# MidDac.net
KiCad netlist of a schematic drawn in Altium Designer
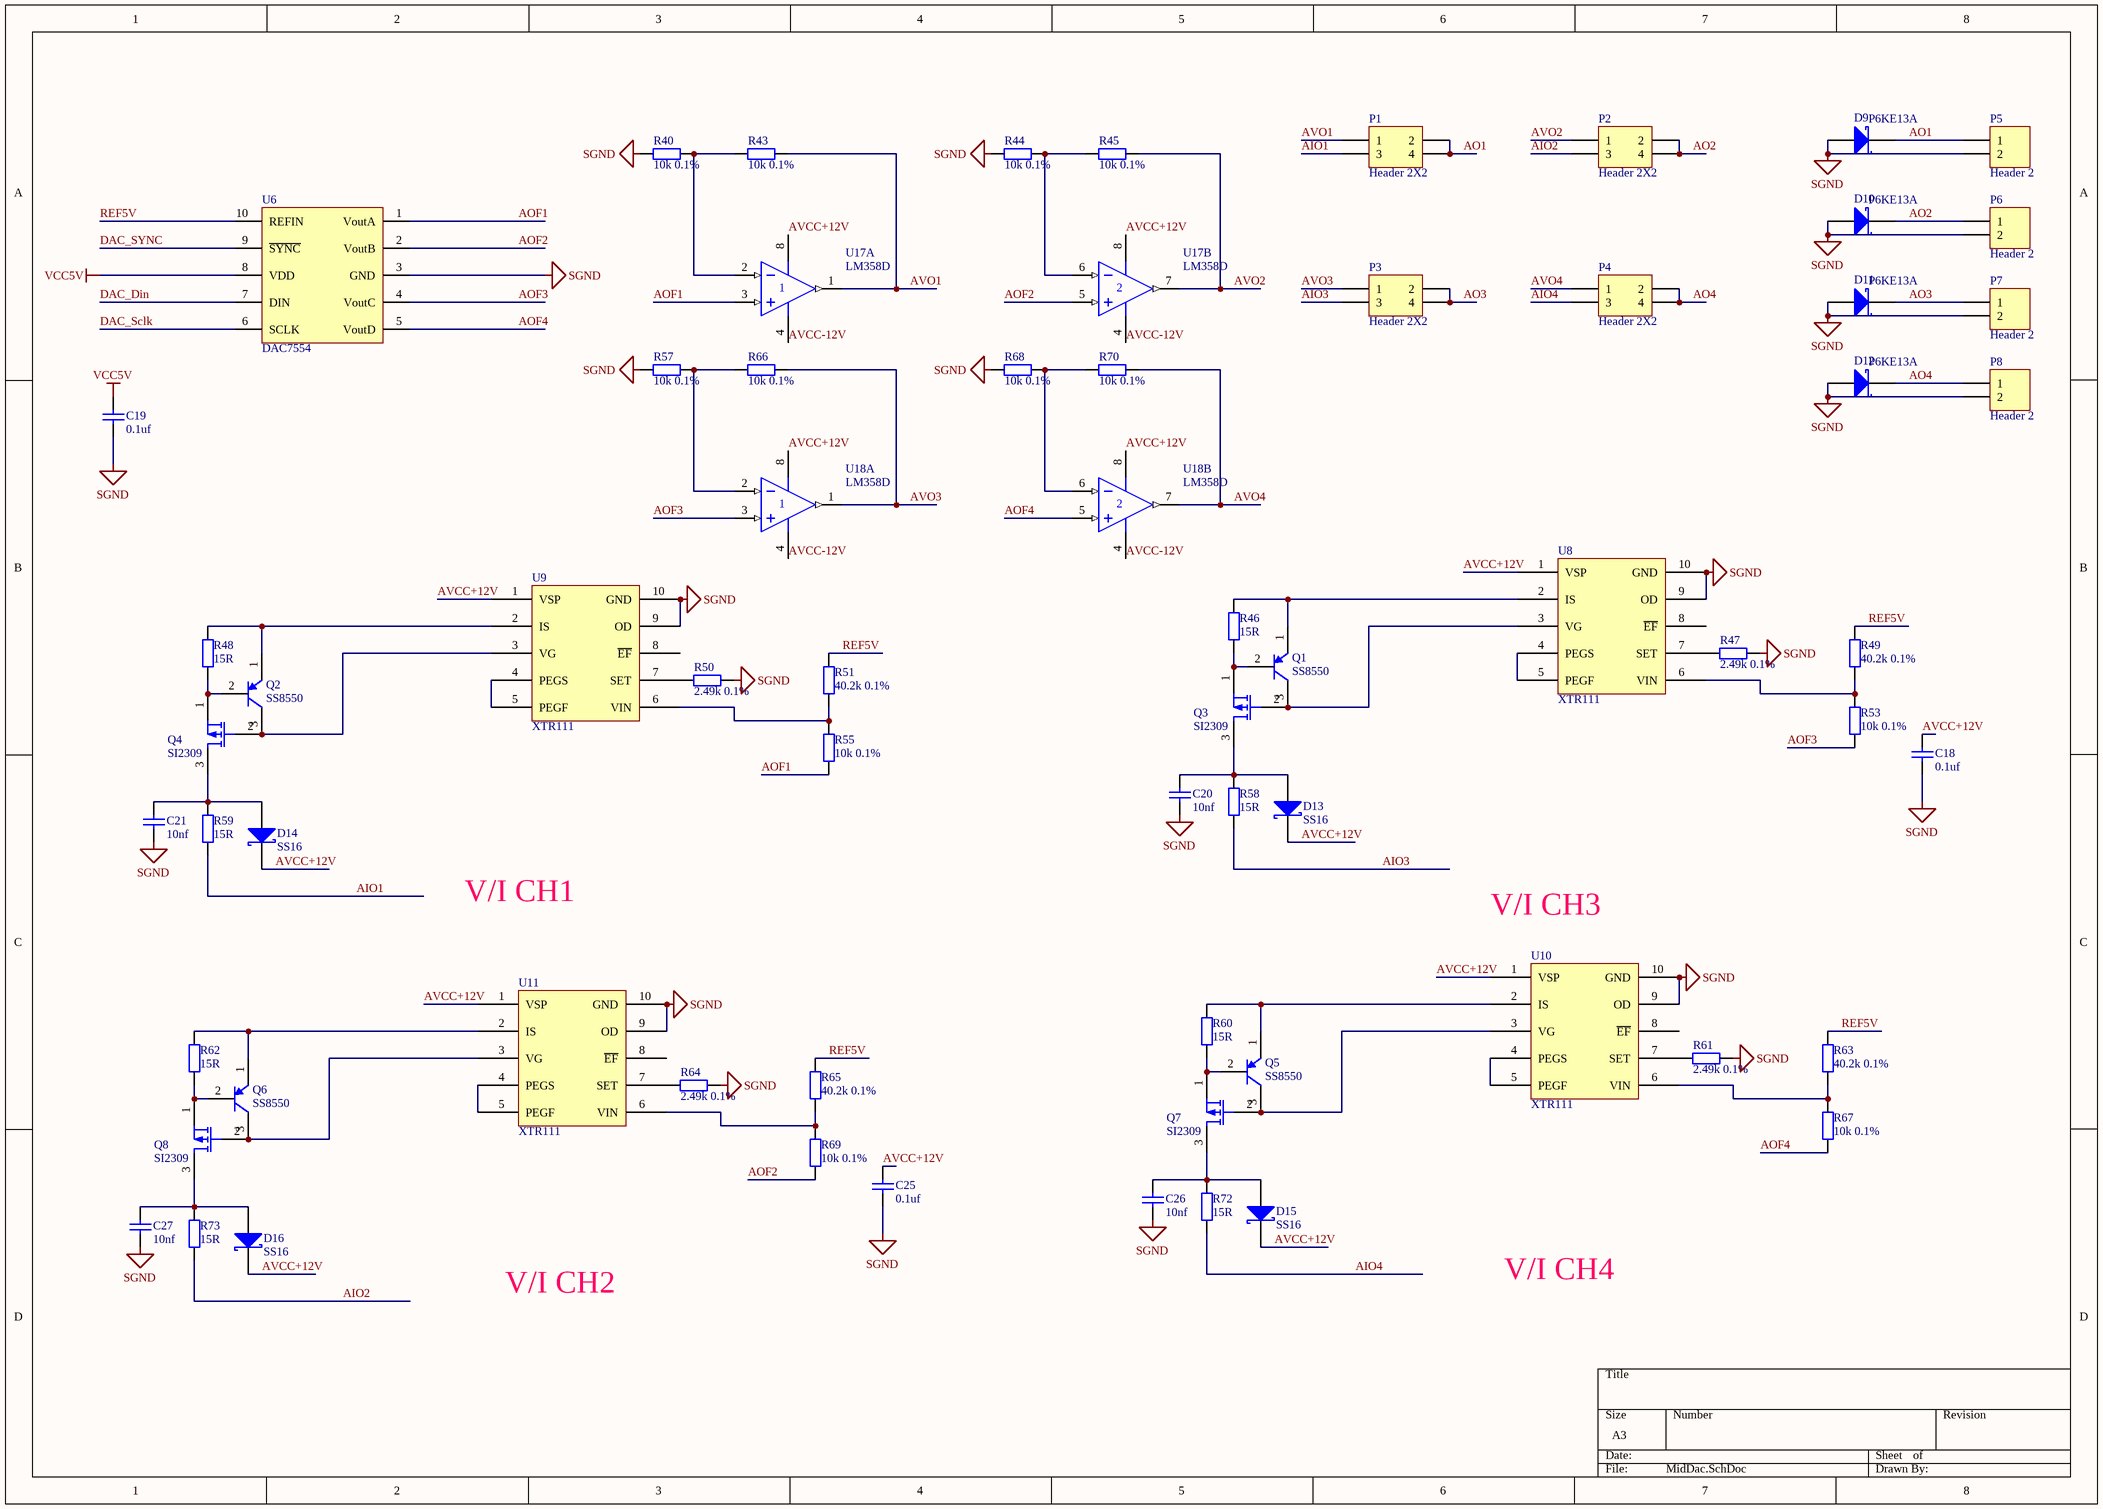
[diagram p0: MidDac.SchDoc]

(export (version "E")
  (design (tool "Eeschema 10.0.6"))
  (components
    (comp (ref "C18")
      (value "0.1uf")
      (footprint "C0805")
      (description "Capacitor")
      (fields
        (field (name "MANUFACTURER") "Generic Components")
        (field (name "Comment") "Cap")
        (field (name "PUBLISHER") "Altium Hobart Technology Centre")
      )
      (libsource (lib "Miscellaneous Devices") (part "Cap"))
    )
    (comp (ref "C19")
      (value "0.1uf")
      (footprint "C0805")
      (description "Capacitor")
      (fields
        (field (name "MANUFACTURER") "Generic Components")
        (field (name "Comment") "Cap")
        (field (name "PUBLISHER") "Altium Hobart Technology Centre")
      )
      (libsource (lib "Miscellaneous Devices") (part "Cap"))
    )
    (comp (ref "C20")
      (value "10nf")
      (footprint "C0805")
      (description "Capacitor")
      (fields
        (field (name "MANUFACTURER") "Generic Components")
        (field (name "Comment") "Cap")
        (field (name "PUBLISHER") "Altium Hobart Technology Centre")
      )
      (libsource (lib "Miscellaneous Devices") (part "Cap"))
    )
    (comp (ref "C21")
      (value "10nf")
      (footprint "C0805")
      (description "Capacitor")
      (fields
        (field (name "MANUFACTURER") "Generic Components")
        (field (name "Comment") "Cap")
        (field (name "PUBLISHER") "Altium Hobart Technology Centre")
      )
      (libsource (lib "Miscellaneous Devices") (part "Cap"))
    )
    (comp (ref "C25")
      (value "0.1uf")
      (footprint "C0805")
      (description "Capacitor")
      (fields
        (field (name "MANUFACTURER") "Generic Components")
        (field (name "Comment") "Cap")
        (field (name "PUBLISHER") "Altium Hobart Technology Centre")
      )
      (libsource (lib "Miscellaneous Devices") (part "Cap"))
    )
    (comp (ref "C26")
      (value "10nf")
      (footprint "C0805")
      (description "Capacitor")
      (fields
        (field (name "MANUFACTURER") "Generic Components")
        (field (name "Comment") "Cap")
        (field (name "PUBLISHER") "Altium Hobart Technology Centre")
      )
      (libsource (lib "Miscellaneous Devices") (part "Cap"))
    )
    (comp (ref "C27")
      (value "10nf")
      (footprint "C0805")
      (description "Capacitor")
      (fields
        (field (name "MANUFACTURER") "Generic Components")
        (field (name "Comment") "Cap")
        (field (name "PUBLISHER") "Altium Hobart Technology Centre")
      )
      (libsource (lib "Miscellaneous Devices") (part "Cap"))
    )
    (comp (ref "D9")
      (value "P6KE13A")
      (footprint "SMB")
      (description "Schottky Diode")
      (fields (field (name "PUBLISHER") "Altium Limited"))
      (libsource (lib "Miscellaneous Devices") (part "D Schottky"))
    )
    (comp (ref "D10")
      (value "P6KE13A")
      (footprint "SMB")
      (description "Schottky Diode")
      (fields (field (name "PUBLISHER") "Altium Limited"))
      (libsource (lib "Miscellaneous Devices") (part "D Schottky"))
    )
    (comp (ref "D11")
      (value "P6KE13A")
      (footprint "SMB")
      (description "Schottky Diode")
      (fields (field (name "PUBLISHER") "Altium Limited"))
      (libsource (lib "Miscellaneous Devices") (part "D Schottky"))
    )
    (comp (ref "D12")
      (value "P6KE13A")
      (footprint "SMB")
      (description "Schottky Diode")
      (fields (field (name "PUBLISHER") "Altium Limited"))
      (libsource (lib "Miscellaneous Devices") (part "D Schottky"))
    )
    (comp (ref "D13")
      (value "SS16")
      (footprint "SMB")
      (description "Schottky Diode")
      (fields (field (name "PUBLISHER") "Altium Limited"))
      (libsource (lib "Miscellaneous Devices") (part "D Schottky"))
    )
    (comp (ref "D14")
      (value "SS16")
      (footprint "SMB")
      (description "Schottky Diode")
      (fields (field (name "PUBLISHER") "Altium Limited"))
      (libsource (lib "Miscellaneous Devices") (part "D Schottky"))
    )
    (comp (ref "D15")
      (value "SS16")
      (footprint "SMB")
      (description "Schottky Diode")
      (fields (field (name "PUBLISHER") "Altium Limited"))
      (libsource (lib "Miscellaneous Devices") (part "D Schottky"))
    )
    (comp (ref "D16")
      (value "SS16")
      (footprint "SMB")
      (description "Schottky Diode")
      (fields (field (name "PUBLISHER") "Altium Limited"))
      (libsource (lib "Miscellaneous Devices") (part "D Schottky"))
    )
    (comp (ref "P1")
      (value "Header 2X2")
      (footprint "HDR2X2")
      (description "Header, 2-Pin, Dual row")
      (fields (field (name "PUBLISHER") "Altium Limited"))
      (libsource (lib "Miscellaneous Connectors") (part "Header 2X2"))
    )
    (comp (ref "P2")
      (value "Header 2X2")
      (footprint "HDR2X2")
      (description "Header, 2-Pin, Dual row")
      (fields (field (name "PUBLISHER") "Altium Limited"))
      (libsource (lib "Miscellaneous Connectors") (part "Header 2X2"))
    )
    (comp (ref "P3")
      (value "Header 2X2")
      (footprint "HDR2X2")
      (description "Header, 2-Pin, Dual row")
      (fields (field (name "PUBLISHER") "Altium Limited"))
      (libsource (lib "Miscellaneous Connectors") (part "Header 2X2"))
    )
    (comp (ref "P4")
      (value "Header 2X2")
      (footprint "HDR2X2")
      (description "Header, 2-Pin, Dual row")
      (fields (field (name "PUBLISHER") "Altium Limited"))
      (libsource (lib "Miscellaneous Connectors") (part "Header 2X2"))
    )
    (comp (ref "P5")
      (value "Header 2")
      (footprint "3.5-P2")
      (description "Header, 2-Pin")
      (fields (field (name "PUBLISHER") "Altium Limited"))
      (libsource (lib "Miscellaneous Connectors") (part "Header 2"))
    )
    (comp (ref "P6")
      (value "Header 2")
      (footprint "3.5-P2")
      (description "Header, 2-Pin")
      (fields (field (name "PUBLISHER") "Altium Limited"))
      (libsource (lib "Miscellaneous Connectors") (part "Header 2"))
    )
    (comp (ref "P7")
      (value "Header 2")
      (footprint "3.5-P2")
      (description "Header, 2-Pin")
      (fields (field (name "PUBLISHER") "Altium Limited"))
      (libsource (lib "Miscellaneous Connectors") (part "Header 2"))
    )
    (comp (ref "P8")
      (value "Header 2")
      (footprint "3.5-P2")
      (description "Header, 2-Pin")
      (fields (field (name "PUBLISHER") "Altium Limited"))
      (libsource (lib "Miscellaneous Connectors") (part "Header 2"))
    )
    (comp (ref "Q1")
      (value "SS8550")
      (footprint "sot-23")
      (description "PNP General Purpose Amplifier")
      (fields (field (name "PUBLISHER") "Altium Limited"))
      (libsource (lib "Miscellaneous Devices") (part "2N3906"))
    )
    (comp (ref "Q2")
      (value "SS8550")
      (footprint "sot-23")
      (description "PNP General Purpose Amplifier")
      (fields (field (name "PUBLISHER") "Altium Limited"))
      (libsource (lib "Miscellaneous Devices") (part "2N3906"))
    )
    (comp (ref "Q3")
      (value "SI2309")
      (footprint "sot-23")
      (description "P-Channel MOSFET")
      (fields (field (name "PUBLISHER") "Altium Limited"))
      (libsource (lib "Miscellaneous Devices") (part "MOSFET-P"))
    )
    (comp (ref "Q4")
      (value "SI2309")
      (footprint "sot-23")
      (description "P-Channel MOSFET")
      (fields (field (name "PUBLISHER") "Altium Limited"))
      (libsource (lib "Miscellaneous Devices") (part "MOSFET-P"))
    )
    (comp (ref "Q5")
      (value "SS8550")
      (footprint "sot-23")
      (description "PNP General Purpose Amplifier")
      (fields (field (name "PUBLISHER") "Altium Limited"))
      (libsource (lib "Miscellaneous Devices") (part "2N3906"))
    )
    (comp (ref "Q6")
      (value "SS8550")
      (footprint "sot-23")
      (description "PNP General Purpose Amplifier")
      (fields (field (name "PUBLISHER") "Altium Limited"))
      (libsource (lib "Miscellaneous Devices") (part "2N3906"))
    )
    (comp (ref "Q7")
      (value "SI2309")
      (footprint "sot-23")
      (description "P-Channel MOSFET")
      (fields (field (name "PUBLISHER") "Altium Limited"))
      (libsource (lib "Miscellaneous Devices") (part "MOSFET-P"))
    )
    (comp (ref "Q8")
      (value "SI2309")
      (footprint "sot-23")
      (description "P-Channel MOSFET")
      (fields (field (name "PUBLISHER") "Altium Limited"))
      (libsource (lib "Miscellaneous Devices") (part "MOSFET-P"))
    )
    (comp (ref "R40")
      (value "10k 0.1%")
      (footprint "0805")
      (fields (field (name "Comment") "Res2"))
      (libsource (lib "") (part "RES_1"))
    )
    (comp (ref "R43")
      (value "10k 0.1%")
      (footprint "0805")
      (fields (field (name "Comment") "Res2"))
      (libsource (lib "") (part "RES_1"))
    )
    (comp (ref "R44")
      (value "10k 0.1%")
      (footprint "0805")
      (fields (field (name "Comment") "Res2"))
      (libsource (lib "") (part "RES_1"))
    )
    (comp (ref "R45")
      (value "10k 0.1%")
      (footprint "0805")
      (fields (field (name "Comment") "Res2"))
      (libsource (lib "") (part "RES_1"))
    )
    (comp (ref "R46")
      (value "15R")
      (footprint "0805")
      (fields (field (name "Comment") "Res2"))
      (libsource (lib "S1") (part "RES"))
    )
    (comp (ref "R47")
      (value "2.49k 0.1%")
      (footprint "0805")
      (fields (field (name "Comment") "Res2"))
      (libsource (lib "") (part "RES_2"))
    )
    (comp (ref "R48")
      (value "15R")
      (footprint "0805")
      (fields (field (name "Comment") "Res2"))
      (libsource (lib "S1") (part "RES"))
    )
    (comp (ref "R49")
      (value "40.2k 0.1%")
      (footprint "0805")
      (fields (field (name "Comment") "Res2"))
      (libsource (lib "S1") (part "RES"))
    )
    (comp (ref "R50")
      (value "2.49k 0.1%")
      (footprint "0805")
      (fields (field (name "Comment") "Res2"))
      (libsource (lib "") (part "RES_2"))
    )
    (comp (ref "R51")
      (value "40.2k 0.1%")
      (footprint "0805")
      (fields (field (name "Comment") "Res2"))
      (libsource (lib "S1") (part "RES"))
    )
    (comp (ref "R53")
      (value "10k 0.1%")
      (footprint "0805")
      (fields (field (name "Comment") "Res2"))
      (libsource (lib "S1") (part "RES"))
    )
    (comp (ref "R55")
      (value "10k 0.1%")
      (footprint "0805")
      (fields (field (name "Comment") "Res2"))
      (libsource (lib "S1") (part "RES"))
    )
    (comp (ref "R57")
      (value "10k 0.1%")
      (footprint "0805")
      (fields (field (name "Comment") "Res2"))
      (libsource (lib "") (part "RES_1"))
    )
    (comp (ref "R58")
      (value "15R")
      (footprint "0805")
      (fields (field (name "Comment") "Res2"))
      (libsource (lib "S1") (part "RES"))
    )
    (comp (ref "R59")
      (value "15R")
      (footprint "0805")
      (fields (field (name "Comment") "Res2"))
      (libsource (lib "S1") (part "RES"))
    )
    (comp (ref "R60")
      (value "15R")
      (footprint "0805")
      (fields (field (name "Comment") "Res2"))
      (libsource (lib "S1") (part "RES"))
    )
    (comp (ref "R61")
      (value "2.49k 0.1%")
      (footprint "0805")
      (fields (field (name "Comment") "Res2"))
      (libsource (lib "") (part "RES_2"))
    )
    (comp (ref "R62")
      (value "15R")
      (footprint "0805")
      (fields (field (name "Comment") "Res2"))
      (libsource (lib "S1") (part "RES"))
    )
    (comp (ref "R63")
      (value "40.2k 0.1%")
      (footprint "0805")
      (fields (field (name "Comment") "Res2"))
      (libsource (lib "S1") (part "RES"))
    )
    (comp (ref "R64")
      (value "2.49k 0.1%")
      (footprint "0805")
      (fields (field (name "Comment") "Res2"))
      (libsource (lib "") (part "RES_2"))
    )
    (comp (ref "R65")
      (value "40.2k 0.1%")
      (footprint "0805")
      (fields (field (name "Comment") "Res2"))
      (libsource (lib "S1") (part "RES"))
    )
    (comp (ref "R66")
      (value "10k 0.1%")
      (footprint "0805")
      (fields (field (name "Comment") "Res2"))
      (libsource (lib "") (part "RES_1"))
    )
    (comp (ref "R67")
      (value "10k 0.1%")
      (footprint "0805")
      (fields (field (name "Comment") "Res2"))
      (libsource (lib "S1") (part "RES"))
    )
    (comp (ref "R68")
      (value "10k 0.1%")
      (footprint "0805")
      (fields (field (name "Comment") "Res2"))
      (libsource (lib "") (part "RES_1"))
    )
    (comp (ref "R69")
      (value "10k 0.1%")
      (footprint "0805")
      (fields (field (name "Comment") "Res2"))
      (libsource (lib "S1") (part "RES"))
    )
    (comp (ref "R70")
      (value "10k 0.1%")
      (footprint "0805")
      (fields (field (name "Comment") "Res2"))
      (libsource (lib "") (part "RES_1"))
    )
    (comp (ref "R72")
      (value "15R")
      (footprint "0805")
      (fields (field (name "Comment") "Res2"))
      (libsource (lib "S1") (part "RES"))
    )
    (comp (ref "R73")
      (value "15R")
      (footprint "0805")
      (fields (field (name "Comment") "Res2"))
      (libsource (lib "S1") (part "RES"))
    )
    (comp (ref "U6") (value "DAC7554") (footprint "VSSOP10") (libsource (lib "常用器件库_SCH") (part "DAC7554")))
    (comp (ref "U8") (value "XTR111") (footprint "TSSOP-10_P") (libsource (lib "斜测仪") (part "XTR111")))
    (comp (ref "U9") (value "XTR111") (footprint "TSSOP-10_P") (libsource (lib "斜测仪") (part "XTR111")))
    (comp (ref "U10") (value "XTR111") (footprint "TSSOP-10_P") (libsource (lib "斜测仪") (part "XTR111")))
    (comp (ref "U11") (value "XTR111") (footprint "TSSOP-10_P") (libsource (lib "斜测仪") (part "XTR111")))
    (comp (ref "U17")
      (value "LM358D")
      (footprint "751-02_N")
      (description "Dual Low-Power Operational Amplifier")
      (fields (field (name "PUBLISHER") "Altium Limited"))
      (libsource (lib "Motorola Amplifier Operational Amplifier") (part "LM358D"))
    )
    (comp (ref "U18")
      (value "LM358D")
      (footprint "751-02_N")
      (description "Dual Low-Power Operational Amplifier")
      (fields (field (name "PUBLISHER") "Altium Limited"))
      (libsource (lib "Motorola Amplifier Operational Amplifier") (part "LM358D"))
    )
  )
  (nets
    (net (code "1") (name "/AIO1") (class "Default")
      (node (ref "P1") (pin "3") (pinfunction "3_3") (pintype "passive"))
      (node (ref "R59") (pin "2") (pinfunction "2_2") (pintype "passive"))
    )
    (net (code "2") (name "/AIO2") (class "Default")
      (node (ref "P2") (pin "3") (pinfunction "3_3") (pintype "passive"))
      (node (ref "R73") (pin "2") (pinfunction "2_2") (pintype "passive"))
    )
    (net (code "3") (name "/AIO3") (class "Default")
      (node (ref "P3") (pin "3") (pinfunction "3_3") (pintype "passive"))
      (node (ref "R58") (pin "2") (pinfunction "2_2") (pintype "passive"))
    )
    (net (code "4") (name "/AIO4") (class "Default")
      (node (ref "P4") (pin "3") (pinfunction "3_3") (pintype "passive"))
      (node (ref "R72") (pin "2") (pinfunction "2_2") (pintype "passive"))
    )
    (net (code "5") (name "/AO1") (class "Default")
      (node (ref "D9") (pin "2") (pinfunction "K_2") (pintype "passive"))
      (node (ref "P1") (pin "2") (pinfunction "2_2") (pintype "passive"))
      (node (ref "P1") (pin "4") (pinfunction "4_4") (pintype "passive"))
      (node (ref "P5") (pin "1") (pinfunction "1_1") (pintype "passive"))
    )
    (net (code "6") (name "/AO2") (class "Default")
      (node (ref "D10") (pin "2") (pinfunction "K_2") (pintype "passive"))
      (node (ref "P2") (pin "2") (pinfunction "2_2") (pintype "passive"))
      (node (ref "P2") (pin "4") (pinfunction "4_4") (pintype "passive"))
      (node (ref "P6") (pin "1") (pinfunction "1_1") (pintype "passive"))
    )
    (net (code "7") (name "/AO3") (class "Default")
      (node (ref "D11") (pin "2") (pinfunction "K_2") (pintype "passive"))
      (node (ref "P3") (pin "2") (pinfunction "2_2") (pintype "passive"))
      (node (ref "P3") (pin "4") (pinfunction "4_4") (pintype "passive"))
      (node (ref "P7") (pin "1") (pinfunction "1_1") (pintype "passive"))
    )
    (net (code "8") (name "/AO4") (class "Default")
      (node (ref "D12") (pin "2") (pinfunction "K_2") (pintype "passive"))
      (node (ref "P4") (pin "2") (pinfunction "2_2") (pintype "passive"))
      (node (ref "P4") (pin "4") (pinfunction "4_4") (pintype "passive"))
      (node (ref "P8") (pin "1") (pinfunction "1_1") (pintype "passive"))
    )
    (net (code "9") (name "/AOF1") (class "Default")
      (node (ref "R55") (pin "2") (pinfunction "2_2") (pintype "passive"))
      (node (ref "U17") (pin "3") (pinfunction "IN+_3") (pintype "input"))
      (node (ref "U6") (pin "1") (pinfunction "VoutA_1") (pintype "passive"))
    )
    (net (code "10") (name "/AOF2") (class "Default")
      (node (ref "R69") (pin "2") (pinfunction "2_2") (pintype "passive"))
      (node (ref "U17") (pin "5") (pinfunction "IN+_5") (pintype "input"))
      (node (ref "U6") (pin "2") (pinfunction "VoutB_2") (pintype "passive"))
    )
    (net (code "11") (name "/AOF3") (class "Default")
      (node (ref "R53") (pin "2") (pinfunction "2_2") (pintype "passive"))
      (node (ref "U18") (pin "3") (pinfunction "IN+_3") (pintype "input"))
      (node (ref "U6") (pin "4") (pinfunction "VoutC_4") (pintype "passive"))
    )
    (net (code "12") (name "/AOF4") (class "Default")
      (node (ref "R67") (pin "2") (pinfunction "2_2") (pintype "passive"))
      (node (ref "U18") (pin "5") (pinfunction "IN+_5") (pintype "input"))
      (node (ref "U6") (pin "5") (pinfunction "VoutD_5") (pintype "passive"))
    )
    (net (code "13") (name "/AVCC+12V") (class "Default")
      (node (ref "C18") (pin "1") (pinfunction "1_1") (pintype "passive"))
      (node (ref "C25") (pin "1") (pinfunction "1_1") (pintype "passive"))
      (node (ref "D13") (pin "2") (pinfunction "K_2") (pintype "passive"))
      (node (ref "D14") (pin "2") (pinfunction "K_2") (pintype "passive"))
      (node (ref "D15") (pin "2") (pinfunction "K_2") (pintype "passive"))
      (node (ref "D16") (pin "2") (pinfunction "K_2") (pintype "passive"))
      (node (ref "U10") (pin "1") (pinfunction "VSP_1") (pintype "passive"))
      (node (ref "U11") (pin "1") (pinfunction "VSP_1") (pintype "passive"))
      (node (ref "U17") (pin "8") (pinfunction "V+_8") (pintype "power_in"))
      (node (ref "U18") (pin "8") (pinfunction "V+_8") (pintype "power_in"))
      (node (ref "U8") (pin "1") (pinfunction "VSP_1") (pintype "passive"))
      (node (ref "U9") (pin "1") (pinfunction "VSP_1") (pintype "passive"))
    )
    (net (code "14") (name "/AVCC-12V") (class "Default")
      (node (ref "U17") (pin "4") (pinfunction "V-_4") (pintype "power_in"))
      (node (ref "U18") (pin "4") (pinfunction "V-_4") (pintype "power_in"))
    )
    (net (code "15") (name "/AVO1") (class "Default")
      (node (ref "P1") (pin "1") (pinfunction "1_1") (pintype "passive"))
      (node (ref "R43") (pin "2") (pinfunction "2_2") (pintype "passive"))
      (node (ref "U17") (pin "1") (pinfunction "OUT_1") (pintype "output"))
    )
    (net (code "16") (name "/AVO2") (class "Default")
      (node (ref "P2") (pin "1") (pinfunction "1_1") (pintype "passive"))
      (node (ref "R45") (pin "2") (pinfunction "2_2") (pintype "passive"))
      (node (ref "U17") (pin "7") (pinfunction "OUT_7") (pintype "output"))
    )
    (net (code "17") (name "/AVO3") (class "Default")
      (node (ref "P3") (pin "1") (pinfunction "1_1") (pintype "passive"))
      (node (ref "R66") (pin "2") (pinfunction "2_2") (pintype "passive"))
      (node (ref "U18") (pin "1") (pinfunction "OUT_1") (pintype "output"))
    )
    (net (code "18") (name "/AVO4") (class "Default")
      (node (ref "P4") (pin "1") (pinfunction "1_1") (pintype "passive"))
      (node (ref "R70") (pin "2") (pinfunction "2_2") (pintype "passive"))
      (node (ref "U18") (pin "7") (pinfunction "OUT_7") (pintype "output"))
    )
    (net (code "19") (name "/DAC_Din") (class "Default")
      (node (ref "U6") (pin "7") (pinfunction "DIN_7") (pintype "passive"))
    )
    (net (code "20") (name "/DAC_SYNC") (class "Default")
      (node (ref "U6") (pin "9") (pinfunction "~{SYNC}_9") (pintype "passive"))
    )
    (net (code "21") (name "/DAC_Sclk") (class "Default")
      (node (ref "U6") (pin "6") (pinfunction "SCLK_6") (pintype "passive"))
    )
    (net (code "22") (name "/REF5V") (class "Default")
      (node (ref "R49") (pin "1") (pinfunction "1_1") (pintype "passive"))
      (node (ref "R51") (pin "1") (pinfunction "1_1") (pintype "passive"))
      (node (ref "R63") (pin "1") (pinfunction "1_1") (pintype "passive"))
      (node (ref "R65") (pin "1") (pinfunction "1_1") (pintype "passive"))
      (node (ref "U6") (pin "10") (pinfunction "REFIN_10") (pintype "passive"))
    )
    (net (code "23") (name "Net-(D13-A)") (class "Default")
      (node (ref "C20") (pin "1") (pinfunction "1_1") (pintype "passive"))
      (node (ref "D13") (pin "1") (pinfunction "A_1") (pintype "passive"))
      (node (ref "Q3") (pin "3") (pinfunction "D_3") (pintype "passive"))
      (node (ref "R58") (pin "1") (pinfunction "1_1") (pintype "passive"))
    )
    (net (code "24") (name "Net-(D14-A)") (class "Default")
      (node (ref "C21") (pin "1") (pinfunction "1_1") (pintype "passive"))
      (node (ref "D14") (pin "1") (pinfunction "A_1") (pintype "passive"))
      (node (ref "Q4") (pin "3") (pinfunction "D_3") (pintype "passive"))
      (node (ref "R59") (pin "1") (pinfunction "1_1") (pintype "passive"))
    )
    (net (code "25") (name "Net-(D15-A)") (class "Default")
      (node (ref "C26") (pin "1") (pinfunction "1_1") (pintype "passive"))
      (node (ref "D15") (pin "1") (pinfunction "A_1") (pintype "passive"))
      (node (ref "Q7") (pin "3") (pinfunction "D_3") (pintype "passive"))
      (node (ref "R72") (pin "1") (pinfunction "1_1") (pintype "passive"))
    )
    (net (code "26") (name "Net-(D16-A)") (class "Default")
      (node (ref "C27") (pin "1") (pinfunction "1_1") (pintype "passive"))
      (node (ref "D16") (pin "1") (pinfunction "A_1") (pintype "passive"))
      (node (ref "Q8") (pin "3") (pinfunction "D_3") (pintype "passive"))
      (node (ref "R73") (pin "1") (pinfunction "1_1") (pintype "passive"))
    )
    (net (code "27") (name "Net-(Q1-B)") (class "Default")
      (node (ref "Q1") (pin "2") (pinfunction "B_2") (pintype "passive"))
      (node (ref "Q3") (pin "1") (pinfunction "S_1") (pintype "passive"))
      (node (ref "R46") (pin "2") (pinfunction "2_2") (pintype "passive"))
    )
    (net (code "28") (name "Net-(Q1-C)") (class "Default")
      (node (ref "Q1") (pin "3") (pinfunction "C_3") (pintype "passive"))
      (node (ref "Q3") (pin "2") (pinfunction "G_2") (pintype "passive"))
      (node (ref "U8") (pin "3") (pinfunction "VG_3") (pintype "passive"))
    )
    (net (code "29") (name "Net-(Q1-E)") (class "Default")
      (node (ref "Q1") (pin "1") (pinfunction "E_1") (pintype "passive"))
      (node (ref "R46") (pin "1") (pinfunction "1_1") (pintype "passive"))
      (node (ref "U8") (pin "2") (pinfunction "IS_2") (pintype "passive"))
    )
    (net (code "30") (name "Net-(Q2-B)") (class "Default")
      (node (ref "Q2") (pin "2") (pinfunction "B_2") (pintype "passive"))
      (node (ref "Q4") (pin "1") (pinfunction "S_1") (pintype "passive"))
      (node (ref "R48") (pin "2") (pinfunction "2_2") (pintype "passive"))
    )
    (net (code "31") (name "Net-(Q2-C)") (class "Default")
      (node (ref "Q2") (pin "3") (pinfunction "C_3") (pintype "passive"))
      (node (ref "Q4") (pin "2") (pinfunction "G_2") (pintype "passive"))
      (node (ref "U9") (pin "3") (pinfunction "VG_3") (pintype "passive"))
    )
    (net (code "32") (name "Net-(Q2-E)") (class "Default")
      (node (ref "Q2") (pin "1") (pinfunction "E_1") (pintype "passive"))
      (node (ref "R48") (pin "1") (pinfunction "1_1") (pintype "passive"))
      (node (ref "U9") (pin "2") (pinfunction "IS_2") (pintype "passive"))
    )
    (net (code "33") (name "Net-(Q5-B)") (class "Default")
      (node (ref "Q5") (pin "2") (pinfunction "B_2") (pintype "passive"))
      (node (ref "Q7") (pin "1") (pinfunction "S_1") (pintype "passive"))
      (node (ref "R60") (pin "2") (pinfunction "2_2") (pintype "passive"))
    )
    (net (code "34") (name "Net-(Q5-C)") (class "Default")
      (node (ref "Q5") (pin "3") (pinfunction "C_3") (pintype "passive"))
      (node (ref "Q7") (pin "2") (pinfunction "G_2") (pintype "passive"))
      (node (ref "U10") (pin "3") (pinfunction "VG_3") (pintype "passive"))
    )
    (net (code "35") (name "Net-(Q5-E)") (class "Default")
      (node (ref "Q5") (pin "1") (pinfunction "E_1") (pintype "passive"))
      (node (ref "R60") (pin "1") (pinfunction "1_1") (pintype "passive"))
      (node (ref "U10") (pin "2") (pinfunction "IS_2") (pintype "passive"))
    )
    (net (code "36") (name "Net-(Q6-B)") (class "Default")
      (node (ref "Q6") (pin "2") (pinfunction "B_2") (pintype "passive"))
      (node (ref "Q8") (pin "1") (pinfunction "S_1") (pintype "passive"))
      (node (ref "R62") (pin "2") (pinfunction "2_2") (pintype "passive"))
    )
    (net (code "37") (name "Net-(Q6-C)") (class "Default")
      (node (ref "Q6") (pin "3") (pinfunction "C_3") (pintype "passive"))
      (node (ref "Q8") (pin "2") (pinfunction "G_2") (pintype "passive"))
      (node (ref "U11") (pin "3") (pinfunction "VG_3") (pintype "passive"))
    )
    (net (code "38") (name "Net-(Q6-E)") (class "Default")
      (node (ref "Q6") (pin "1") (pinfunction "E_1") (pintype "passive"))
      (node (ref "R62") (pin "1") (pinfunction "1_1") (pintype "passive"))
      (node (ref "U11") (pin "2") (pinfunction "IS_2") (pintype "passive"))
    )
    (net (code "39") (name "Net-(U8-PEGF)") (class "Default")
      (node (ref "U8") (pin "4") (pinfunction "PEGS_4") (pintype "passive"))
      (node (ref "U8") (pin "5") (pinfunction "PEGF_5") (pintype "passive"))
    )
    (net (code "40") (name "Net-(U8-SET)") (class "Default")
      (node (ref "R47") (pin "1") (pinfunction "1_1") (pintype "passive"))
      (node (ref "U8") (pin "7") (pinfunction "SET_7") (pintype "passive"))
    )
    (net (code "41") (name "Net-(U8-VIN)") (class "Default")
      (node (ref "R49") (pin "2") (pinfunction "2_2") (pintype "passive"))
      (node (ref "R53") (pin "1") (pinfunction "1_1") (pintype "passive"))
      (node (ref "U8") (pin "6") (pinfunction "VIN_6") (pintype "passive"))
    )
    (net (code "42") (name "Net-(U9-PEGF)") (class "Default")
      (node (ref "U9") (pin "4") (pinfunction "PEGS_4") (pintype "passive"))
      (node (ref "U9") (pin "5") (pinfunction "PEGF_5") (pintype "passive"))
    )
    (net (code "43") (name "Net-(U9-SET)") (class "Default")
      (node (ref "R50") (pin "1") (pinfunction "1_1") (pintype "passive"))
      (node (ref "U9") (pin "7") (pinfunction "SET_7") (pintype "passive"))
    )
    (net (code "44") (name "Net-(U9-VIN)") (class "Default")
      (node (ref "R51") (pin "2") (pinfunction "2_2") (pintype "passive"))
      (node (ref "R55") (pin "1") (pinfunction "1_1") (pintype "passive"))
      (node (ref "U9") (pin "6") (pinfunction "VIN_6") (pintype "passive"))
    )
    (net (code "45") (name "Net-(U10-PEGF)") (class "Default")
      (node (ref "U10") (pin "4") (pinfunction "PEGS_4") (pintype "passive"))
      (node (ref "U10") (pin "5") (pinfunction "PEGF_5") (pintype "passive"))
    )
    (net (code "46") (name "Net-(U10-SET)") (class "Default")
      (node (ref "R61") (pin "1") (pinfunction "1_1") (pintype "passive"))
      (node (ref "U10") (pin "7") (pinfunction "SET_7") (pintype "passive"))
    )
    (net (code "47") (name "Net-(U10-VIN)") (class "Default")
      (node (ref "R63") (pin "2") (pinfunction "2_2") (pintype "passive"))
      (node (ref "R67") (pin "1") (pinfunction "1_1") (pintype "passive"))
      (node (ref "U10") (pin "6") (pinfunction "VIN_6") (pintype "passive"))
    )
    (net (code "48") (name "Net-(U11-PEGF)") (class "Default")
      (node (ref "U11") (pin "4") (pinfunction "PEGS_4") (pintype "passive"))
      (node (ref "U11") (pin "5") (pinfunction "PEGF_5") (pintype "passive"))
    )
    (net (code "49") (name "Net-(U11-SET)") (class "Default")
      (node (ref "R64") (pin "1") (pinfunction "1_1") (pintype "passive"))
      (node (ref "U11") (pin "7") (pinfunction "SET_7") (pintype "passive"))
    )
    (net (code "50") (name "Net-(U11-VIN)") (class "Default")
      (node (ref "R65") (pin "2") (pinfunction "2_2") (pintype "passive"))
      (node (ref "R69") (pin "1") (pinfunction "1_1") (pintype "passive"))
      (node (ref "U11") (pin "6") (pinfunction "VIN_6") (pintype "passive"))
    )
    (net (code "51") (name "Net-(U17A-IN-)") (class "Default")
      (node (ref "R40") (pin "2") (pinfunction "2_2") (pintype "passive"))
      (node (ref "R43") (pin "1") (pinfunction "1_1") (pintype "passive"))
      (node (ref "U17") (pin "2") (pinfunction "IN-_2") (pintype "input"))
    )
    (net (code "52") (name "Net-(U17B-IN-)") (class "Default")
      (node (ref "R44") (pin "2") (pinfunction "2_2") (pintype "passive"))
      (node (ref "R45") (pin "1") (pinfunction "1_1") (pintype "passive"))
      (node (ref "U17") (pin "6") (pinfunction "IN-_6") (pintype "input"))
    )
    (net (code "53") (name "Net-(U18A-IN-)") (class "Default")
      (node (ref "R57") (pin "2") (pinfunction "2_2") (pintype "passive"))
      (node (ref "R66") (pin "1") (pinfunction "1_1") (pintype "passive"))
      (node (ref "U18") (pin "2") (pinfunction "IN-_2") (pintype "input"))
    )
    (net (code "54") (name "Net-(U18B-IN-)") (class "Default")
      (node (ref "R68") (pin "2") (pinfunction "2_2") (pintype "passive"))
      (node (ref "R70") (pin "1") (pinfunction "1_1") (pintype "passive"))
      (node (ref "U18") (pin "6") (pinfunction "IN-_6") (pintype "input"))
    )
    (net (code "55") (name "SGND") (class "Default")
      (node (ref "C18") (pin "2") (pinfunction "2_2") (pintype "passive"))
      (node (ref "C19") (pin "2") (pinfunction "2_2") (pintype "passive"))
      (node (ref "C20") (pin "2") (pinfunction "2_2") (pintype "passive"))
      (node (ref "C21") (pin "2") (pinfunction "2_2") (pintype "passive"))
      (node (ref "C25") (pin "2") (pinfunction "2_2") (pintype "passive"))
      (node (ref "C26") (pin "2") (pinfunction "2_2") (pintype "passive"))
      (node (ref "C27") (pin "2") (pinfunction "2_2") (pintype "passive"))
      (node (ref "D10") (pin "1") (pinfunction "A_1") (pintype "passive"))
      (node (ref "D11") (pin "1") (pinfunction "A_1") (pintype "passive"))
      (node (ref "D12") (pin "1") (pinfunction "A_1") (pintype "passive"))
      (node (ref "D9") (pin "1") (pinfunction "A_1") (pintype "passive"))
      (node (ref "P5") (pin "2") (pinfunction "2_2") (pintype "passive"))
      (node (ref "P6") (pin "2") (pinfunction "2_2") (pintype "passive"))
      (node (ref "P7") (pin "2") (pinfunction "2_2") (pintype "passive"))
      (node (ref "P8") (pin "2") (pinfunction "2_2") (pintype "passive"))
      (node (ref "R40") (pin "1") (pinfunction "1_1") (pintype "passive"))
      (node (ref "R44") (pin "1") (pinfunction "1_1") (pintype "passive"))
      (node (ref "R47") (pin "2") (pinfunction "2_2") (pintype "passive"))
      (node (ref "R50") (pin "2") (pinfunction "2_2") (pintype "passive"))
      (node (ref "R57") (pin "1") (pinfunction "1_1") (pintype "passive"))
      (node (ref "R61") (pin "2") (pinfunction "2_2") (pintype "passive"))
      (node (ref "R64") (pin "2") (pinfunction "2_2") (pintype "passive"))
      (node (ref "R68") (pin "1") (pinfunction "1_1") (pintype "passive"))
      (node (ref "U10") (pin "10") (pinfunction "GND_10") (pintype "passive"))
      (node (ref "U10") (pin "9") (pinfunction "OD_9") (pintype "passive"))
      (node (ref "U11") (pin "10") (pinfunction "GND_10") (pintype "passive"))
      (node (ref "U11") (pin "9") (pinfunction "OD_9") (pintype "passive"))
      (node (ref "U6") (pin "3") (pinfunction "GND_3") (pintype "passive"))
      (node (ref "U8") (pin "10") (pinfunction "GND_10") (pintype "passive"))
      (node (ref "U8") (pin "9") (pinfunction "OD_9") (pintype "passive"))
      (node (ref "U9") (pin "10") (pinfunction "GND_10") (pintype "passive"))
      (node (ref "U9") (pin "9") (pinfunction "OD_9") (pintype "passive"))
    )
    (net (code "56") (name "VCC5V") (class "Default")
      (node (ref "C19") (pin "1") (pinfunction "1_1") (pintype "passive"))
      (node (ref "U6") (pin "8") (pinfunction "VDD_8") (pintype "passive"))
    )
    (net (code "57") (name "unconnected-(U8-~{EF}-Pad8)") (class "Default")
      (node (ref "U8") (pin "8") (pinfunction "~{EF}_8") (pintype "passive"))
    )
    (net (code "58") (name "unconnected-(U9-~{EF}-Pad8)") (class "Default")
      (node (ref "U9") (pin "8") (pinfunction "~{EF}_8") (pintype "passive"))
    )
    (net (code "59") (name "unconnected-(U10-~{EF}-Pad8)") (class "Default")
      (node (ref "U10") (pin "8") (pinfunction "~{EF}_8") (pintype "passive"))
    )
    (net (code "60") (name "unconnected-(U11-~{EF}-Pad8)") (class "Default")
      (node (ref "U11") (pin "8") (pinfunction "~{EF}_8") (pintype "passive"))
    )
  )
)
